# POWER.net
KiCad netlist of a schematic drawn in Altium Designer
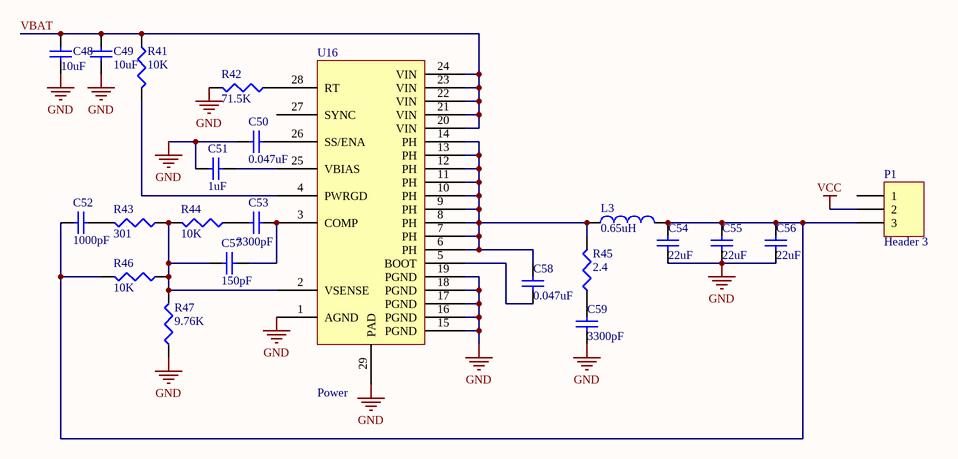
[diagram p0: POWER.SchDoc]

(export (version "E")
  (design (tool "Eeschema 10.0.6"))
  (components
    (comp (ref "C48")
      (value "10uF")
      (footprint "CAPC1005L")
      (description "Capacitor (Semiconductor SIM Model)")
      (fields (field (name "Comment") "Cap Semi") (field (name "PUBLISHER") "Altium Limited"))
      (libsource (lib "Miscellaneous Devices") (part "Cap Semi"))
    )
    (comp (ref "C49")
      (value "10uF")
      (footprint "CAPC1005L")
      (description "Capacitor (Semiconductor SIM Model)")
      (fields (field (name "Comment") "Cap Semi") (field (name "PUBLISHER") "Altium Limited"))
      (libsource (lib "Miscellaneous Devices") (part "Cap Semi"))
    )
    (comp (ref "C50")
      (value "0.047uF")
      (footprint "CAPC1005L")
      (description "Capacitor (Semiconductor SIM Model)")
      (fields (field (name "Comment") "Cap Semi") (field (name "PUBLISHER") "Altium Limited"))
      (libsource (lib "Miscellaneous Devices") (part "Cap Semi"))
    )
    (comp (ref "C51")
      (value "1uF")
      (footprint "CAPC1005L")
      (description "Capacitor (Semiconductor SIM Model)")
      (fields (field (name "Comment") "Cap Semi") (field (name "PUBLISHER") "Altium Limited"))
      (libsource (lib "Miscellaneous Devices") (part "Cap Semi"))
    )
    (comp (ref "C52")
      (value "1000pF")
      (footprint "CAPC1005L")
      (description "Capacitor (Semiconductor SIM Model)")
      (fields (field (name "Comment") "Cap Semi") (field (name "PUBLISHER") "Altium Limited"))
      (libsource (lib "Miscellaneous Devices") (part "Cap Semi"))
    )
    (comp (ref "C53")
      (value "3300pF")
      (footprint "CAPC1005L")
      (description "Capacitor (Semiconductor SIM Model)")
      (fields (field (name "Comment") "Cap Semi") (field (name "PUBLISHER") "Altium Limited"))
      (libsource (lib "Miscellaneous Devices") (part "Cap Semi"))
    )
    (comp (ref "C54")
      (value "22uF")
      (footprint "CAPC1005L")
      (description "Capacitor (Semiconductor SIM Model)")
      (fields (field (name "Comment") "Cap Semi") (field (name "PUBLISHER") "Altium Limited"))
      (libsource (lib "Miscellaneous Devices") (part "Cap Semi"))
    )
    (comp (ref "C55")
      (value "22uF")
      (footprint "CAPC1005L")
      (description "Capacitor (Semiconductor SIM Model)")
      (fields (field (name "Comment") "Cap Semi") (field (name "PUBLISHER") "Altium Limited"))
      (libsource (lib "Miscellaneous Devices") (part "Cap Semi"))
    )
    (comp (ref "C56")
      (value "22uF")
      (footprint "CAPC1005L")
      (description "Capacitor (Semiconductor SIM Model)")
      (fields (field (name "Comment") "Cap Semi") (field (name "PUBLISHER") "Altium Limited"))
      (libsource (lib "Miscellaneous Devices") (part "Cap Semi"))
    )
    (comp (ref "C57")
      (value "150pF")
      (footprint "CAPC1005L")
      (description "Capacitor (Semiconductor SIM Model)")
      (fields (field (name "Comment") "Cap Semi") (field (name "PUBLISHER") "Altium Limited"))
      (libsource (lib "Miscellaneous Devices") (part "Cap Semi"))
    )
    (comp (ref "C58")
      (value "0.047uF")
      (footprint "CAPC1005L")
      (description "Capacitor (Semiconductor SIM Model)")
      (fields (field (name "Comment") "Cap Semi") (field (name "PUBLISHER") "Altium Limited"))
      (libsource (lib "Miscellaneous Devices") (part "Cap Semi"))
    )
    (comp (ref "C59")
      (value "3300pF")
      (footprint "CAPC1005L")
      (description "Capacitor (Semiconductor SIM Model)")
      (fields (field (name "Comment") "Cap Semi") (field (name "PUBLISHER") "Altium Limited"))
      (libsource (lib "Miscellaneous Devices") (part "Cap Semi"))
    )
    (comp (ref "L3") (value "0.65uH") (footprint "IndPow") (libsource (lib "mrone") (part "Inductor")))
    (comp (ref "P1")
      (value "Header 3")
      (footprint "HDR1X3")
      (description "Header, 3-Pin")
      (fields (field (name "PUBLISHER") "Altium Limited"))
      (libsource (lib "Miscellaneous Connectors") (part "Header 3"))
    )
    (comp (ref "R41")
      (value "10K")
      (footprint "RESC1608L")
      (description "Resistor")
      (fields (field (name "Comment") "Res3") (field (name "PUBLISHER") "Altium Limited"))
      (libsource (lib "Miscellaneous Devices") (part "Res3"))
    )
    (comp (ref "R42")
      (value "71.5K")
      (footprint "RESC1608L")
      (description "Resistor")
      (fields (field (name "Comment") "Res3") (field (name "PUBLISHER") "Altium Limited"))
      (libsource (lib "Miscellaneous Devices") (part "Res3"))
    )
    (comp (ref "R43")
      (value "301")
      (footprint "RESC1608L")
      (description "Resistor")
      (fields (field (name "Comment") "Res3") (field (name "PUBLISHER") "Altium Limited"))
      (libsource (lib "Miscellaneous Devices") (part "Res3"))
    )
    (comp (ref "R44")
      (value "10K")
      (footprint "RESC1608L")
      (description "Resistor")
      (fields (field (name "Comment") "Res3") (field (name "PUBLISHER") "Altium Limited"))
      (libsource (lib "Miscellaneous Devices") (part "Res3"))
    )
    (comp (ref "R45")
      (value "2.4")
      (footprint "RESC1608L")
      (description "Resistor")
      (fields (field (name "Comment") "Res3") (field (name "PUBLISHER") "Altium Limited"))
      (libsource (lib "Miscellaneous Devices") (part "Res3"))
    )
    (comp (ref "R46")
      (value "10K")
      (footprint "RESC1608L")
      (description "Resistor")
      (fields (field (name "Comment") "Res3") (field (name "PUBLISHER") "Altium Limited"))
      (libsource (lib "Miscellaneous Devices") (part "Res3"))
    )
    (comp (ref "R47")
      (value "9.76K")
      (footprint "RESC1608L")
      (description "Resistor")
      (fields (field (name "Comment") "Res3") (field (name "PUBLISHER") "Altium Limited"))
      (libsource (lib "Miscellaneous Devices") (part "Res3"))
    )
    (comp (ref "U16")
      (value "Power")
      (footprint "TSOP_28_PowerPad")
      (libsource (lib "mrone") (part "Power_Switcher"))
    )
  )
  (nets
    (net (code "1") (name "/VBAT") (class "Default")
      (node (ref "C48") (pin "1") (pinfunction "1_1") (pintype "passive"))
      (node (ref "C49") (pin "1") (pinfunction "1_1") (pintype "passive"))
      (node (ref "R41") (pin "1") (pinfunction "1_1") (pintype "passive"))
      (node (ref "U16") (pin "20") (pinfunction "VIN_20") (pintype "passive"))
      (node (ref "U16") (pin "21") (pinfunction "VIN_21") (pintype "passive"))
      (node (ref "U16") (pin "22") (pinfunction "VIN_22") (pintype "passive"))
      (node (ref "U16") (pin "23") (pinfunction "VIN_23") (pintype "passive"))
      (node (ref "U16") (pin "24") (pinfunction "VIN_24") (pintype "passive"))
    )
    (net (code "2") (name "GND") (class "Default")
      (node (ref "C48") (pin "2") (pinfunction "2_2") (pintype "passive"))
      (node (ref "C49") (pin "2") (pinfunction "2_2") (pintype "passive"))
      (node (ref "C50") (pin "2") (pinfunction "2_2") (pintype "passive"))
      (node (ref "C51") (pin "2") (pinfunction "2_2") (pintype "passive"))
      (node (ref "C54") (pin "1") (pinfunction "1_1") (pintype "passive"))
      (node (ref "C55") (pin "1") (pinfunction "1_1") (pintype "passive"))
      (node (ref "C56") (pin "1") (pinfunction "1_1") (pintype "passive"))
      (node (ref "C59") (pin "1") (pinfunction "1_1") (pintype "passive"))
      (node (ref "R42") (pin "2") (pinfunction "2_2") (pintype "passive"))
      (node (ref "R47") (pin "1") (pinfunction "1_1") (pintype "passive"))
      (node (ref "U16") (pin "1") (pinfunction "AGND_1") (pintype "passive"))
      (node (ref "U16") (pin "15") (pinfunction "PGND_15") (pintype "passive"))
      (node (ref "U16") (pin "16") (pinfunction "PGND_16") (pintype "passive"))
      (node (ref "U16") (pin "17") (pinfunction "PGND_17") (pintype "passive"))
      (node (ref "U16") (pin "18") (pinfunction "PGND_18") (pintype "passive"))
      (node (ref "U16") (pin "19") (pinfunction "PGND_19") (pintype "passive"))
      (node (ref "U16") (pin "29") (pinfunction "PAD_29") (pintype "passive"))
    )
    (net (code "3") (name "Net-(C52-Pad1)") (class "Default")
      (node (ref "C52") (pin "1") (pinfunction "1_1") (pintype "passive"))
      (node (ref "C54") (pin "2") (pinfunction "2_2") (pintype "passive"))
      (node (ref "C55") (pin "2") (pinfunction "2_2") (pintype "passive"))
      (node (ref "C56") (pin "2") (pinfunction "2_2") (pintype "passive"))
      (node (ref "L3") (pin "2") (pinfunction "2_2") (pintype "passive"))
      (node (ref "P1") (pin "3") (pinfunction "3_3") (pintype "passive"))
      (node (ref "R46") (pin "2") (pinfunction "2_2") (pintype "passive"))
    )
    (net (code "4") (name "Net-(C52-Pad2)") (class "Default")
      (node (ref "C52") (pin "2") (pinfunction "2_2") (pintype "passive"))
      (node (ref "R43") (pin "2") (pinfunction "2_2") (pintype "passive"))
    )
    (net (code "5") (name "Net-(C53-Pad2)") (class "Default")
      (node (ref "C53") (pin "2") (pinfunction "2_2") (pintype "passive"))
      (node (ref "R44") (pin "1") (pinfunction "1_1") (pintype "passive"))
    )
    (net (code "6") (name "Net-(C58-Pad2)") (class "Default")
      (node (ref "C58") (pin "2") (pinfunction "2_2") (pintype "passive"))
      (node (ref "L3") (pin "1") (pinfunction "1_1") (pintype "passive"))
      (node (ref "R45") (pin "2") (pinfunction "2_2") (pintype "passive"))
      (node (ref "U16") (pin "10") (pinfunction "PH_10") (pintype "passive"))
      (node (ref "U16") (pin "11") (pinfunction "PH_11") (pintype "passive"))
      (node (ref "U16") (pin "12") (pinfunction "PH_12") (pintype "passive"))
      (node (ref "U16") (pin "13") (pinfunction "PH_13") (pintype "passive"))
      (node (ref "U16") (pin "14") (pinfunction "PH_14") (pintype "passive"))
      (node (ref "U16") (pin "6") (pinfunction "PH_6") (pintype "passive"))
      (node (ref "U16") (pin "7") (pinfunction "PH_7") (pintype "passive"))
      (node (ref "U16") (pin "8") (pinfunction "PH_8") (pintype "passive"))
      (node (ref "U16") (pin "9") (pinfunction "PH_9") (pintype "passive"))
    )
    (net (code "7") (name "Net-(C59-Pad2)") (class "Default")
      (node (ref "C59") (pin "2") (pinfunction "2_2") (pintype "passive"))
      (node (ref "R45") (pin "1") (pinfunction "1_1") (pintype "passive"))
    )
    (net (code "8") (name "Net-(U16-BOOT)") (class "Default")
      (node (ref "C58") (pin "1") (pinfunction "1_1") (pintype "passive"))
      (node (ref "U16") (pin "5") (pinfunction "BOOT_5") (pintype "passive"))
    )
    (net (code "9") (name "Net-(U16-COMP)") (class "Default")
      (node (ref "C53") (pin "1") (pinfunction "1_1") (pintype "passive"))
      (node (ref "C57") (pin "1") (pinfunction "1_1") (pintype "passive"))
      (node (ref "U16") (pin "3") (pinfunction "COMP_3") (pintype "passive"))
    )
    (net (code "10") (name "Net-(U16-PWRGD)") (class "Default")
      (node (ref "R41") (pin "2") (pinfunction "2_2") (pintype "passive"))
      (node (ref "U16") (pin "4") (pinfunction "PWRGD_4") (pintype "passive"))
    )
    (net (code "11") (name "Net-(U16-RT)") (class "Default")
      (node (ref "R42") (pin "1") (pinfunction "1_1") (pintype "passive"))
      (node (ref "U16") (pin "28") (pinfunction "RT_28") (pintype "passive"))
    )
    (net (code "12") (name "Net-(U16-SS{slash}ENA)") (class "Default")
      (node (ref "C50") (pin "1") (pinfunction "1_1") (pintype "passive"))
      (node (ref "U16") (pin "26") (pinfunction "SS/ENA_26") (pintype "passive"))
    )
    (net (code "13") (name "Net-(U16-VBIAS)") (class "Default")
      (node (ref "C51") (pin "1") (pinfunction "1_1") (pintype "passive"))
      (node (ref "U16") (pin "25") (pinfunction "VBIAS_25") (pintype "passive"))
    )
    (net (code "14") (name "Net-(U16-VSENSE)") (class "Default")
      (node (ref "C57") (pin "2") (pinfunction "2_2") (pintype "passive"))
      (node (ref "R43") (pin "1") (pinfunction "1_1") (pintype "passive"))
      (node (ref "R44") (pin "2") (pinfunction "2_2") (pintype "passive"))
      (node (ref "R46") (pin "1") (pinfunction "1_1") (pintype "passive"))
      (node (ref "R47") (pin "2") (pinfunction "2_2") (pintype "passive"))
      (node (ref "U16") (pin "2") (pinfunction "VSENSE_2") (pintype "passive"))
    )
    (net (code "15") (name "VCC") (class "Default")
      (node (ref "P1") (pin "2") (pinfunction "2_2") (pintype "passive"))
    )
    (net (code "16") (name "unconnected-(P1-Pad1)") (class "Default")
      (node (ref "P1") (pin "1") (pinfunction "1_1") (pintype "passive"))
    )
    (net (code "17") (name "unconnected-(U16-SYNC-Pad27)") (class "Default")
      (node (ref "U16") (pin "27") (pinfunction "SYNC_27") (pintype "passive"))
    )
  )
)
